# Processor_Interface.net
KiCad netlist of a schematic drawn in Altium Designer
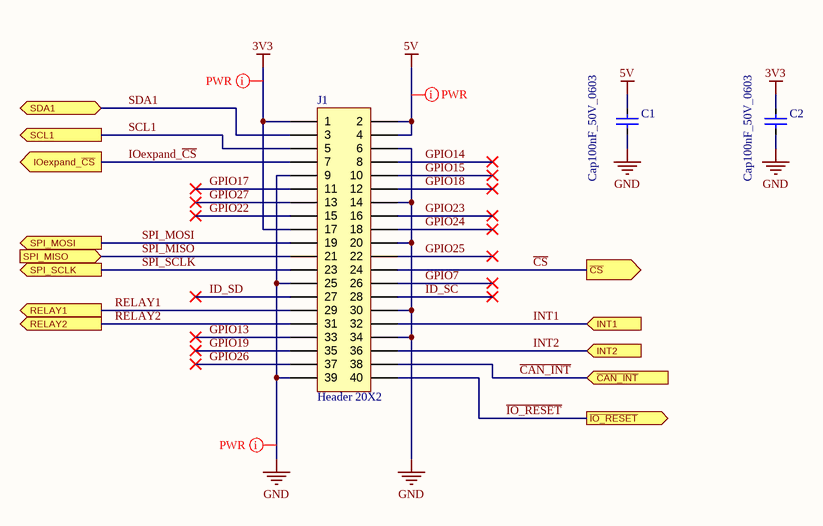
[diagram p0: Processor_Interface.SchDoc]

(export (version "E")
  (design (tool "Eeschema 10.0.6"))
  (components
    (comp (ref "C1")
      (value "Cap100nF_50V_0603")
      (footprint "0603C_L")
      (libsource (lib "Advanced] Training Course - A365") (part "CAP General"))
    )
    (comp (ref "C2")
      (value "Cap100nF_50V_0603")
      (footprint "0603C_L")
      (libsource (lib "Advanced] Training Course - A365") (part "CAP General"))
    )
    (comp (ref "J1")
      (value "Header 20X2")
      (footprint "HDR2X20")
      (description "Header, 20-Pin, Dual row")
      (fields (field (name "PUBLISHER") "Altium Limited"))
      (libsource (lib "Advanced] Training Course - A365") (part "Header 20X2"))
    )
  )
  (nets
    (net (code "1") (name "/CAN_INT") (class "Default")
      (node (ref "J1") (pin "38") (pinfunction "38_38") (pintype "passive"))
    )
    (net (code "2") (name "/GPIO7") (class "Default")
      (node (ref "J1") (pin "26") (pinfunction "26_26") (pintype "passive+no_connect"))
    )
    (net (code "3") (name "/GPIO13") (class "Default")
      (node (ref "J1") (pin "33") (pinfunction "33_33") (pintype "passive+no_connect"))
    )
    (net (code "4") (name "/GPIO14") (class "Default")
      (node (ref "J1") (pin "8") (pinfunction "8_8") (pintype "passive+no_connect"))
    )
    (net (code "5") (name "/GPIO15") (class "Default")
      (node (ref "J1") (pin "10") (pinfunction "10_10") (pintype "passive+no_connect"))
    )
    (net (code "6") (name "/GPIO17") (class "Default")
      (node (ref "J1") (pin "11") (pinfunction "11_11") (pintype "passive+no_connect"))
    )
    (net (code "7") (name "/GPIO18") (class "Default")
      (node (ref "J1") (pin "12") (pinfunction "12_12") (pintype "passive+no_connect"))
    )
    (net (code "8") (name "/GPIO19") (class "Default")
      (node (ref "J1") (pin "35") (pinfunction "35_35") (pintype "passive+no_connect"))
    )
    (net (code "9") (name "/GPIO22") (class "Default")
      (node (ref "J1") (pin "15") (pinfunction "15_15") (pintype "passive+no_connect"))
    )
    (net (code "10") (name "/GPIO23") (class "Default")
      (node (ref "J1") (pin "16") (pinfunction "16_16") (pintype "passive+no_connect"))
    )
    (net (code "11") (name "/GPIO24") (class "Default")
      (node (ref "J1") (pin "18") (pinfunction "18_18") (pintype "passive+no_connect"))
    )
    (net (code "12") (name "/GPIO25") (class "Default")
      (node (ref "J1") (pin "22") (pinfunction "22_22") (pintype "passive+no_connect"))
    )
    (net (code "13") (name "/GPIO26") (class "Default")
      (node (ref "J1") (pin "37") (pinfunction "37_37") (pintype "passive+no_connect"))
    )
    (net (code "14") (name "/GPIO27") (class "Default")
      (node (ref "J1") (pin "13") (pinfunction "13_13") (pintype "passive+no_connect"))
    )
    (net (code "15") (name "/ID_SC") (class "Default")
      (node (ref "J1") (pin "28") (pinfunction "28_28") (pintype "passive+no_connect"))
    )
    (net (code "16") (name "/ID_SD") (class "Default")
      (node (ref "J1") (pin "27") (pinfunction "27_27") (pintype "passive+no_connect"))
    )
    (net (code "17") (name "/INT1") (class "Default")
      (node (ref "J1") (pin "32") (pinfunction "32_32") (pintype "passive"))
    )
    (net (code "18") (name "/INT2") (class "Default")
      (node (ref "J1") (pin "36") (pinfunction "36_36") (pintype "passive"))
    )
    (net (code "19") (name "/IO_RESET") (class "Default")
      (node (ref "J1") (pin "40") (pinfunction "40_40") (pintype "passive"))
    )
    (net (code "20") (name "/IOexpand_~{CS}") (class "Default")
      (node (ref "J1") (pin "7") (pinfunction "7_7") (pintype "passive"))
    )
    (net (code "21") (name "/RELAY1") (class "Default")
      (node (ref "J1") (pin "29") (pinfunction "29_29") (pintype "passive"))
    )
    (net (code "22") (name "/RELAY2") (class "Default")
      (node (ref "J1") (pin "31") (pinfunction "31_31") (pintype "passive"))
    )
    (net (code "23") (name "/SCL1") (class "Default")
      (node (ref "J1") (pin "5") (pinfunction "5_5") (pintype "passive"))
    )
    (net (code "24") (name "/SDA1") (class "Default")
      (node (ref "J1") (pin "3") (pinfunction "3_3") (pintype "passive"))
    )
    (net (code "25") (name "/SPI_MISO") (class "Default")
      (node (ref "J1") (pin "21") (pinfunction "21_21") (pintype "passive"))
    )
    (net (code "26") (name "/SPI_MOSI") (class "Default")
      (node (ref "J1") (pin "19") (pinfunction "19_19") (pintype "passive"))
    )
    (net (code "27") (name "/SPI_SCLK") (class "Default")
      (node (ref "J1") (pin "23") (pinfunction "23_23") (pintype "passive"))
    )
    (net (code "28") (name "/~{CS}") (class "Default")
      (node (ref "J1") (pin "24") (pinfunction "24_24") (pintype "passive"))
    )
    (net (code "29") (name "3V3") (class "Default")
      (node (ref "C2") (pin "2") (pinfunction "2_2") (pintype "passive"))
      (node (ref "J1") (pin "1") (pinfunction "1_1") (pintype "passive"))
      (node (ref "J1") (pin "17") (pinfunction "17_17") (pintype "passive"))
    )
    (net (code "30") (name "5V") (class "Default")
      (node (ref "C1") (pin "2") (pinfunction "2_2") (pintype "passive"))
      (node (ref "J1") (pin "2") (pinfunction "2_2") (pintype "passive"))
      (node (ref "J1") (pin "4") (pinfunction "4_4") (pintype "passive"))
    )
    (net (code "31") (name "GND") (class "Default")
      (node (ref "C1") (pin "1") (pinfunction "1_1") (pintype "passive"))
      (node (ref "C2") (pin "1") (pinfunction "1_1") (pintype "passive"))
      (node (ref "J1") (pin "14") (pinfunction "14_14") (pintype "passive"))
      (node (ref "J1") (pin "20") (pinfunction "20_20") (pintype "passive"))
      (node (ref "J1") (pin "25") (pinfunction "25_25") (pintype "passive"))
      (node (ref "J1") (pin "30") (pinfunction "30_30") (pintype "passive"))
      (node (ref "J1") (pin "34") (pinfunction "34_34") (pintype "passive"))
      (node (ref "J1") (pin "39") (pinfunction "39_39") (pintype "passive"))
      (node (ref "J1") (pin "6") (pinfunction "6_6") (pintype "passive"))
      (node (ref "J1") (pin "9") (pinfunction "9_9") (pintype "passive"))
    )
  )
)
